# SilentStepStick-TMC2208_v12.net
KiCad netlist of a schematic drawn in EAGLE
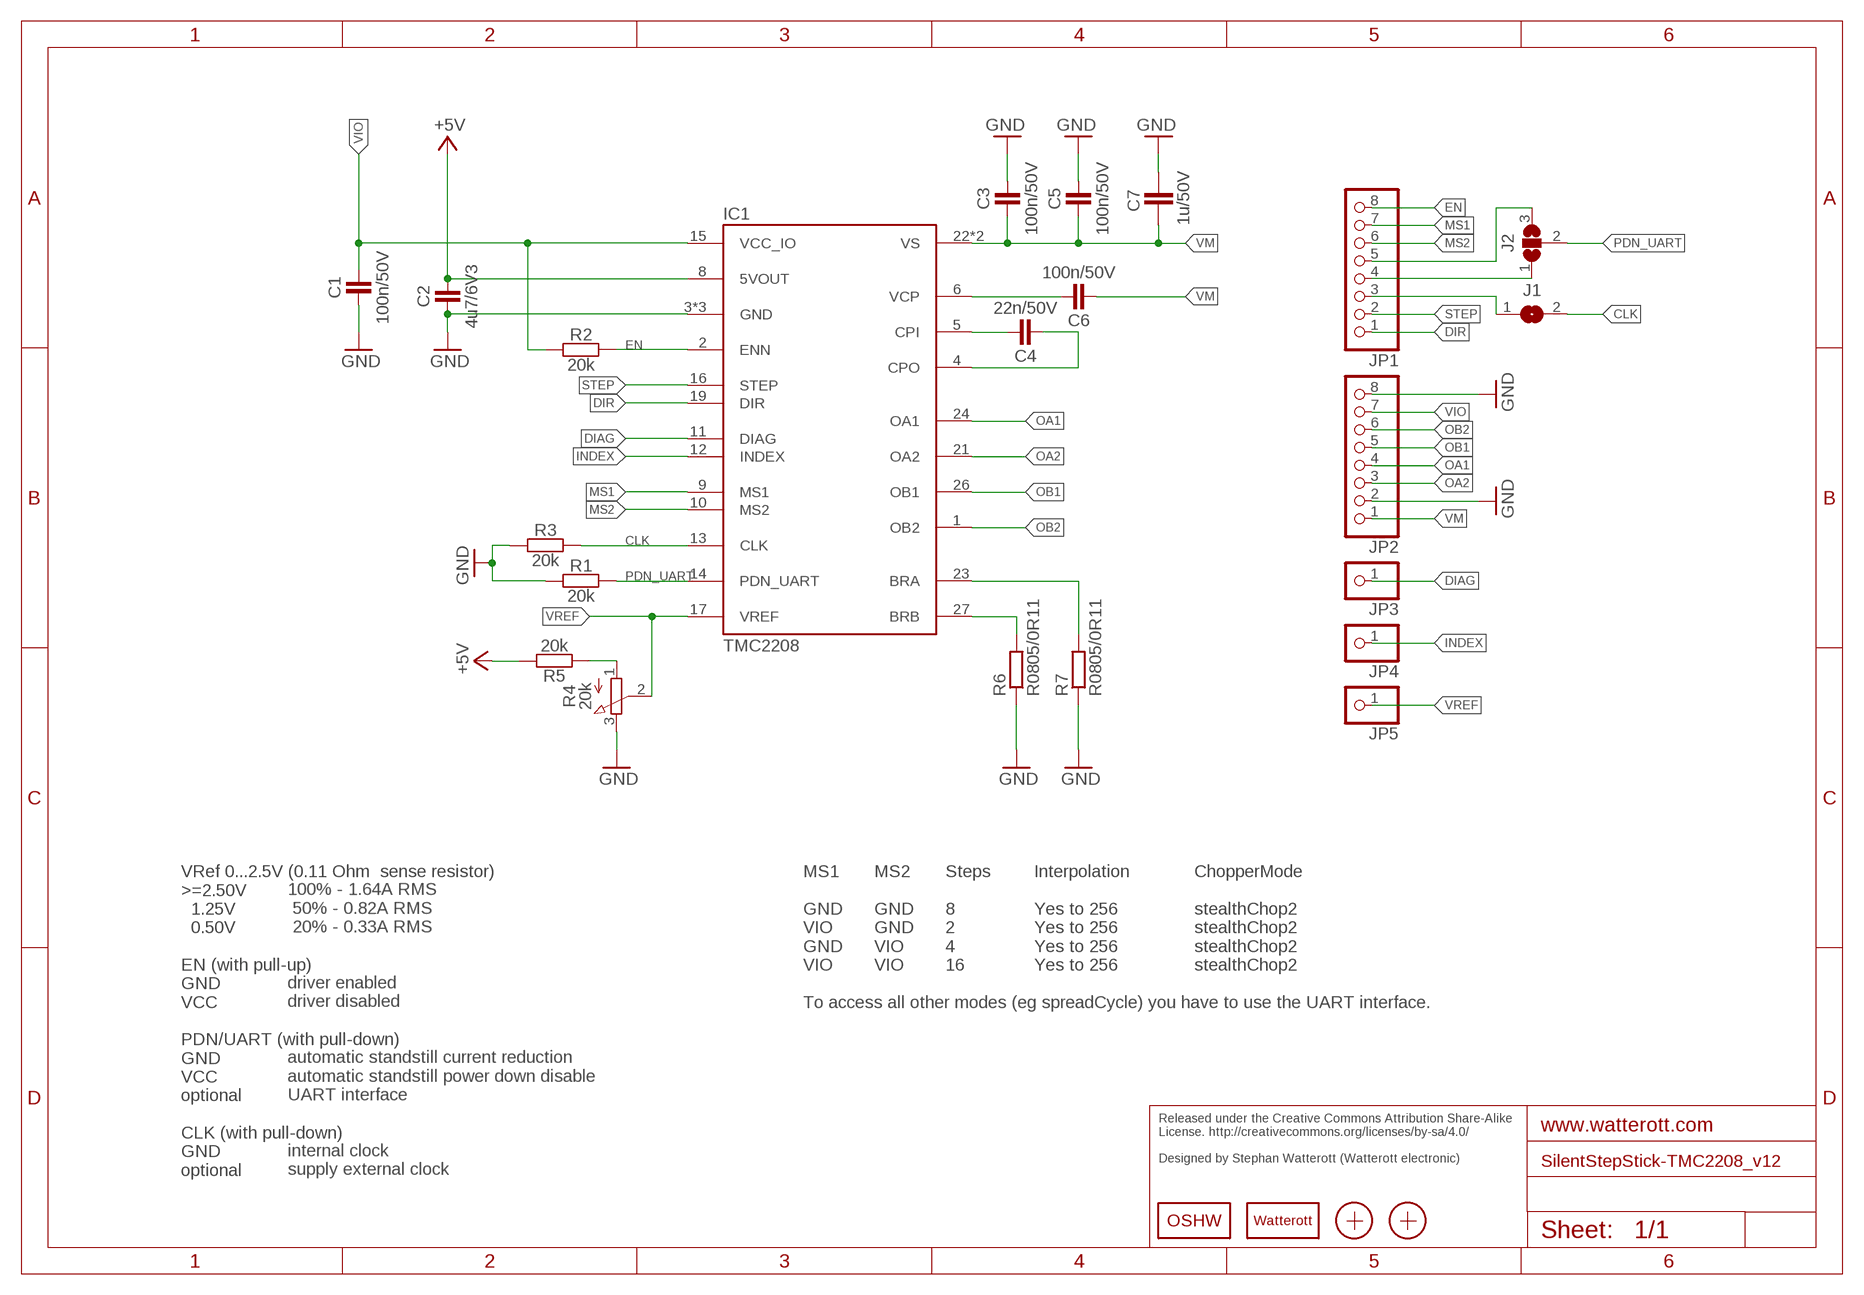
[diagram p0: schematic, sheet 1]

(export (version "E")
  (design (tool "Eeschema 10.0.6"))
  (components
    (comp (ref "C1")
      (value "100n/50V")
      (footprint "eagle-import:C0402")
      (libsource (lib "eagle-import") (part "CAPACITOR-0402"))
    )
    (comp (ref "C2")
      (value "4u7/6V3")
      (footprint "eagle-import:C0402")
      (libsource (lib "eagle-import") (part "CAPACITOR-0402"))
    )
    (comp (ref "C3")
      (value "100n/50V")
      (footprint "eagle-import:C0402")
      (libsource (lib "eagle-import") (part "CAPACITOR-0402"))
    )
    (comp (ref "C4")
      (value "22n/50V")
      (footprint "eagle-import:C0402")
      (libsource (lib "eagle-import") (part "CAPACITOR-0402"))
    )
    (comp (ref "C5")
      (value "100n/50V")
      (footprint "eagle-import:C0402")
      (libsource (lib "eagle-import") (part "CAPACITOR-0402"))
    )
    (comp (ref "C6")
      (value "100n/50V")
      (footprint "eagle-import:C0402")
      (libsource (lib "eagle-import") (part "CAPACITOR-0402"))
    )
    (comp (ref "C7")
      (value "1u/50V")
      (footprint "eagle-import:C0805")
      (libsource (lib "eagle-import") (part "C-EUC0805"))
    )
    (comp (ref "IC1")
      (value "TMC2208")
      (footprint "eagle-import:QFN28-PAD")
      (libsource (lib "eagle-import") (part "TMC2208"))
    )
    (comp (ref "J1")
      (value "JUMPER2-0402")
      (footprint "eagle-import:JUMPER2-0402")
      (libsource (lib "eagle-import") (part "JUMPER2-0402"))
    )
    (comp (ref "J2")
      (value "JUMPER3-0402-NC")
      (footprint "eagle-import:JUMPER3-0402_NC")
      (libsource (lib "eagle-import") (part "JUMPER3-0402-NC"))
    )
    (comp (ref "JP1")
      (value "PINHD-1X08_2.54-S")
      (footprint "eagle-import:1X08-S")
      (libsource (lib "eagle-import") (part "PINHD-1X08_2.54-S"))
    )
    (comp (ref "JP2")
      (value "PINHD-1X08_2.54-S")
      (footprint "eagle-import:1X08-S")
      (libsource (lib "eagle-import") (part "PINHD-1X08_2.54-S"))
    )
    (comp (ref "JP3")
      (value "PINHD-1X1")
      (footprint "eagle-import:1X01")
      (libsource (lib "eagle-import") (part "PINHD-1X1"))
    )
    (comp (ref "JP4")
      (value "PINHD-1X1")
      (footprint "eagle-import:1X01")
      (libsource (lib "eagle-import") (part "PINHD-1X1"))
    )
    (comp (ref "JP5")
      (value "PINHD-1X1")
      (footprint "eagle-import:1X01")
      (libsource (lib "eagle-import") (part "PINHD-1X1"))
    )
    (comp (ref "LOGO1")
      (value "OSHW_LOGOX0070")
      (footprint "eagle-import:OSHW_6X70")
      (libsource (lib "eagle-import") (part "OSHW_LOGOX0070"))
    )
    (comp (ref "LOGO2")
      (value "LOGO-S_PLACE_M")
      (footprint "eagle-import:SPARK_TPLACE_M")
      (libsource (lib "eagle-import") (part "LOGO-S_PLACE_M"))
    )
    (comp (ref "R1")
      (value "20k")
      (footprint "eagle-import:C0402")
      (libsource (lib "eagle-import") (part "RESISTOR-0402"))
    )
    (comp (ref "R2")
      (value "20k")
      (footprint "eagle-import:C0402")
      (libsource (lib "eagle-import") (part "RESISTOR-0402"))
    )
    (comp (ref "R3")
      (value "20k")
      (footprint "eagle-import:C0402")
      (libsource (lib "eagle-import") (part "RESISTOR-0402"))
    )
    (comp (ref "R4")
      (value "20k")
      (footprint "eagle-import:POT_EVM3R")
      (libsource (lib "eagle-import") (part "POT-EVM3R"))
    )
    (comp (ref "R5")
      (value "20k")
      (footprint "eagle-import:C0402")
      (libsource (lib "eagle-import") (part "RESISTOR-0402"))
    )
    (comp (ref "R6")
      (value "R0805/0R11")
      (footprint "eagle-import:M0805")
      (libsource (lib "eagle-import") (part "R-EU_M0805"))
    )
    (comp (ref "R7")
      (value "R0805/0R11")
      (footprint "eagle-import:M0805")
      (libsource (lib "eagle-import") (part "R-EU_M0805"))
    )
    (comp (ref "X1")
      (value "PASSER-04")
      (footprint "eagle-import:PASSER_04MM")
      (libsource (lib "eagle-import") (part "PASSER-04"))
    )
    (comp (ref "X2")
      (value "PASSER-04")
      (footprint "eagle-import:PASSER_04MM")
      (libsource (lib "eagle-import") (part "PASSER-04"))
    )
  )
  (nets
    (net (code "1") (name "+5V") (class "Default")
      (node (ref "C2") (pin "2") (pinfunction "2_2") (pintype "passive"))
      (node (ref "IC1") (pin "8") (pinfunction "5VOUT_8") (pintype "power_in"))
      (node (ref "R5") (pin "2") (pinfunction "2_2") (pintype "passive"))
    )
    (net (code "2") (name "CLK") (class "Default")
      (node (ref "IC1") (pin "13") (pinfunction "CLK_13") (pintype "bidirectional"))
      (node (ref "J1") (pin "2") (pinfunction "2_2") (pintype "passive"))
      (node (ref "R3") (pin "2") (pinfunction "2_2") (pintype "passive"))
    )
    (net (code "3") (name "DIAG") (class "Default")
      (node (ref "IC1") (pin "11") (pinfunction "DIAG_11") (pintype "bidirectional"))
      (node (ref "JP3") (pin "1") (pinfunction "1_1") (pintype "passive"))
    )
    (net (code "4") (name "DIR") (class "Default")
      (node (ref "IC1") (pin "19") (pinfunction "DIR_19") (pintype "bidirectional"))
      (node (ref "JP1") (pin "1") (pinfunction "1_1") (pintype "passive"))
    )
    (net (code "5") (name "EN") (class "Default")
      (node (ref "IC1") (pin "2") (pinfunction "ENN_2") (pintype "bidirectional"))
      (node (ref "JP1") (pin "8") (pinfunction "8_8") (pintype "passive"))
      (node (ref "R2") (pin "2") (pinfunction "2_2") (pintype "passive"))
    )
    (net (code "6") (name "GND") (class "Default")
      (node (ref "C1") (pin "1") (pinfunction "1_1") (pintype "passive"))
      (node (ref "C2") (pin "1") (pinfunction "1_1") (pintype "passive"))
      (node (ref "C3") (pin "2") (pinfunction "2_2") (pintype "passive"))
      (node (ref "C5") (pin "2") (pinfunction "2_2") (pintype "passive"))
      (node (ref "C7") (pin "2") (pinfunction "2_2") (pintype "passive"))
      (node (ref "IC1") (pin "18") (pinfunction "GND_18") (pintype "power_in"))
      (node (ref "IC1") (pin "3") (pinfunction "GND_3") (pintype "power_in"))
      (node (ref "IC1") (pin "TP") (pinfunction "GND_TP") (pintype "power_in"))
      (node (ref "JP2") (pin "2") (pinfunction "2_2") (pintype "passive"))
      (node (ref "JP2") (pin "8") (pinfunction "8_8") (pintype "passive"))
      (node (ref "R1") (pin "1") (pinfunction "1_1") (pintype "passive"))
      (node (ref "R3") (pin "1") (pinfunction "1_1") (pintype "passive"))
      (node (ref "R4") (pin "3") (pinfunction "E_3") (pintype "passive"))
      (node (ref "R6") (pin "1") (pinfunction "1_1") (pintype "passive"))
      (node (ref "R7") (pin "1") (pinfunction "1_1") (pintype "passive"))
    )
    (net (code "7") (name "INDEX") (class "Default")
      (node (ref "IC1") (pin "12") (pinfunction "INDEX_12") (pintype "bidirectional"))
      (node (ref "JP4") (pin "1") (pinfunction "1_1") (pintype "passive"))
    )
    (net (code "8") (name "MS1") (class "Default")
      (node (ref "IC1") (pin "9") (pinfunction "MS1_9") (pintype "bidirectional"))
      (node (ref "JP1") (pin "7") (pinfunction "7_7") (pintype "passive"))
    )
    (net (code "9") (name "MS2") (class "Default")
      (node (ref "IC1") (pin "10") (pinfunction "MS2_10") (pintype "bidirectional"))
      (node (ref "JP1") (pin "6") (pinfunction "6_6") (pintype "passive"))
    )
    (net (code "10") (name "Net-(IC1-BRA)") (class "Default")
      (node (ref "IC1") (pin "23") (pinfunction "BRA_23") (pintype "output"))
      (node (ref "R7") (pin "2") (pinfunction "2_2") (pintype "passive"))
    )
    (net (code "11") (name "Net-(IC1-BRB)") (class "Default")
      (node (ref "IC1") (pin "27") (pinfunction "BRB_27") (pintype "output"))
      (node (ref "R6") (pin "2") (pinfunction "2_2") (pintype "passive"))
    )
    (net (code "12") (name "Net-(IC1-CPI)") (class "Default")
      (node (ref "C4") (pin "2") (pinfunction "2_2") (pintype "passive"))
      (node (ref "IC1") (pin "5") (pinfunction "CPI_5") (pintype "passive"))
    )
    (net (code "13") (name "Net-(IC1-CPO)") (class "Default")
      (node (ref "C4") (pin "1") (pinfunction "1_1") (pintype "passive"))
      (node (ref "IC1") (pin "4") (pinfunction "CPO_4") (pintype "passive"))
    )
    (net (code "14") (name "Net-(IC1-VCP)") (class "Default")
      (node (ref "C6") (pin "2") (pinfunction "2_2") (pintype "passive"))
      (node (ref "IC1") (pin "6") (pinfunction "VCP_6") (pintype "passive"))
    )
    (net (code "15") (name "Net-(J1-Pad1)") (class "Default")
      (node (ref "J1") (pin "1") (pinfunction "1_1") (pintype "passive"))
      (node (ref "JP1") (pin "3") (pinfunction "3_3") (pintype "passive"))
    )
    (net (code "16") (name "Net-(J2-Pad1)") (class "Default")
      (node (ref "J2") (pin "1") (pinfunction "1_1") (pintype "passive"))
      (node (ref "JP1") (pin "4") (pinfunction "4_4") (pintype "passive"))
    )
    (net (code "17") (name "Net-(J2-Pad3)") (class "Default")
      (node (ref "J2") (pin "3") (pinfunction "3_3") (pintype "passive"))
      (node (ref "JP1") (pin "5") (pinfunction "5_5") (pintype "passive"))
    )
    (net (code "18") (name "Net-(R4-A)") (class "Default")
      (node (ref "R4") (pin "1") (pinfunction "A_1") (pintype "passive"))
      (node (ref "R5") (pin "1") (pinfunction "1_1") (pintype "passive"))
    )
    (net (code "19") (name "OA1") (class "Default")
      (node (ref "IC1") (pin "24") (pinfunction "OA1_24") (pintype "output"))
      (node (ref "JP2") (pin "4") (pinfunction "4_4") (pintype "passive"))
    )
    (net (code "20") (name "OA2") (class "Default")
      (node (ref "IC1") (pin "21") (pinfunction "OA2_21") (pintype "output"))
      (node (ref "JP2") (pin "3") (pinfunction "3_3") (pintype "passive"))
    )
    (net (code "21") (name "OB1") (class "Default")
      (node (ref "IC1") (pin "26") (pinfunction "OB1_26") (pintype "output"))
      (node (ref "JP2") (pin "5") (pinfunction "5_5") (pintype "passive"))
    )
    (net (code "22") (name "OB2") (class "Default")
      (node (ref "IC1") (pin "1") (pinfunction "OB2_1") (pintype "output"))
      (node (ref "JP2") (pin "6") (pinfunction "6_6") (pintype "passive"))
    )
    (net (code "23") (name "PDN_UART") (class "Default")
      (node (ref "IC1") (pin "14") (pinfunction "PDN_UART_14") (pintype "bidirectional"))
      (node (ref "J2") (pin "2") (pinfunction "2_2") (pintype "passive"))
      (node (ref "R1") (pin "2") (pinfunction "2_2") (pintype "passive"))
    )
    (net (code "24") (name "STEP") (class "Default")
      (node (ref "IC1") (pin "16") (pinfunction "STEP_16") (pintype "bidirectional"))
      (node (ref "JP1") (pin "2") (pinfunction "2_2") (pintype "passive"))
    )
    (net (code "25") (name "VIO") (class "Default")
      (node (ref "C1") (pin "2") (pinfunction "2_2") (pintype "passive"))
      (node (ref "IC1") (pin "15") (pinfunction "VCC_IO_15") (pintype "power_in"))
      (node (ref "JP2") (pin "7") (pinfunction "7_7") (pintype "passive"))
      (node (ref "R2") (pin "1") (pinfunction "1_1") (pintype "passive"))
    )
    (net (code "26") (name "VM") (class "Default")
      (node (ref "C3") (pin "1") (pinfunction "1_1") (pintype "passive"))
      (node (ref "C5") (pin "1") (pinfunction "1_1") (pintype "passive"))
      (node (ref "C6") (pin "1") (pinfunction "1_1") (pintype "passive"))
      (node (ref "C7") (pin "1") (pinfunction "1_1") (pintype "passive"))
      (node (ref "IC1") (pin "22") (pinfunction "VS_22") (pintype "power_in"))
      (node (ref "IC1") (pin "28") (pinfunction "VS_28") (pintype "power_in"))
      (node (ref "JP2") (pin "1") (pinfunction "1_1") (pintype "passive"))
    )
    (net (code "27") (name "VREF") (class "Default")
      (node (ref "IC1") (pin "17") (pinfunction "VREF_17") (pintype "passive"))
      (node (ref "JP5") (pin "1") (pinfunction "1_1") (pintype "passive"))
      (node (ref "R4") (pin "2") (pinfunction "S_2") (pintype "passive"))
    )
  )
)
